# SSTuino_Evo.net
KiCad netlist of a schematic drawn in EAGLE
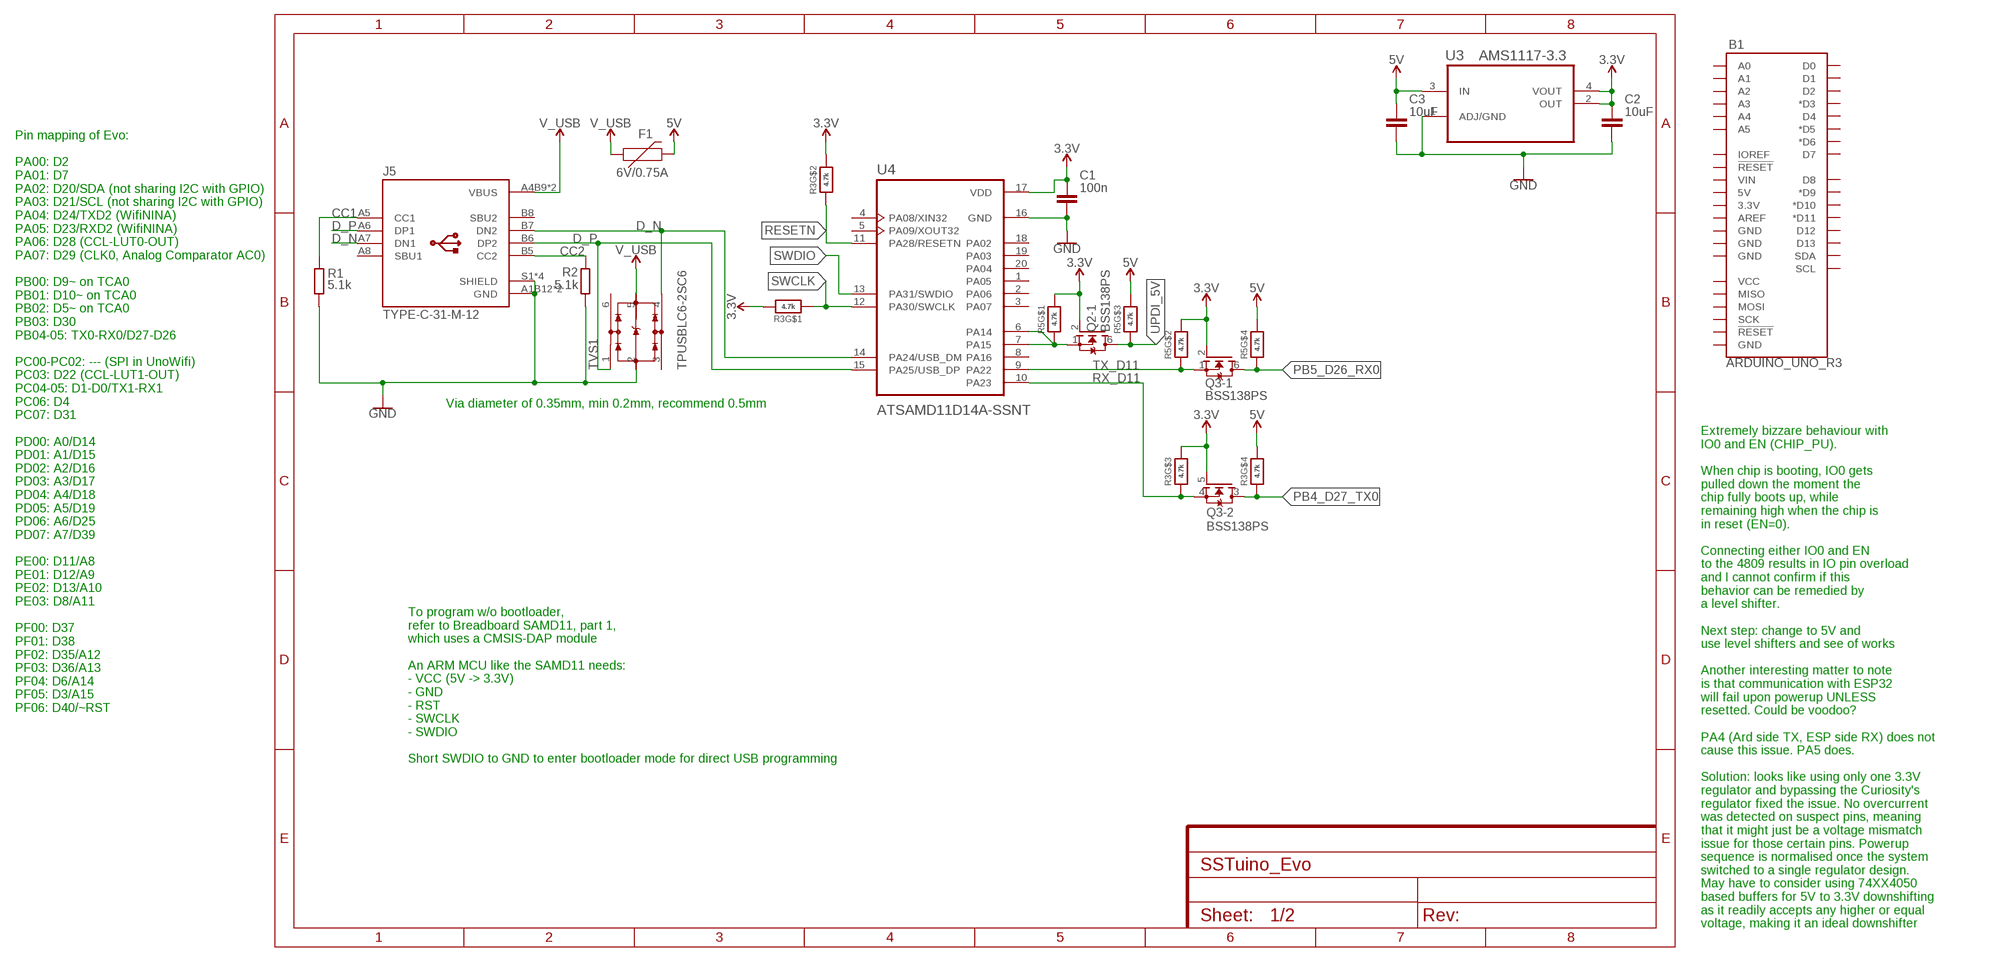
[diagram p0: schematic, sheet 1]
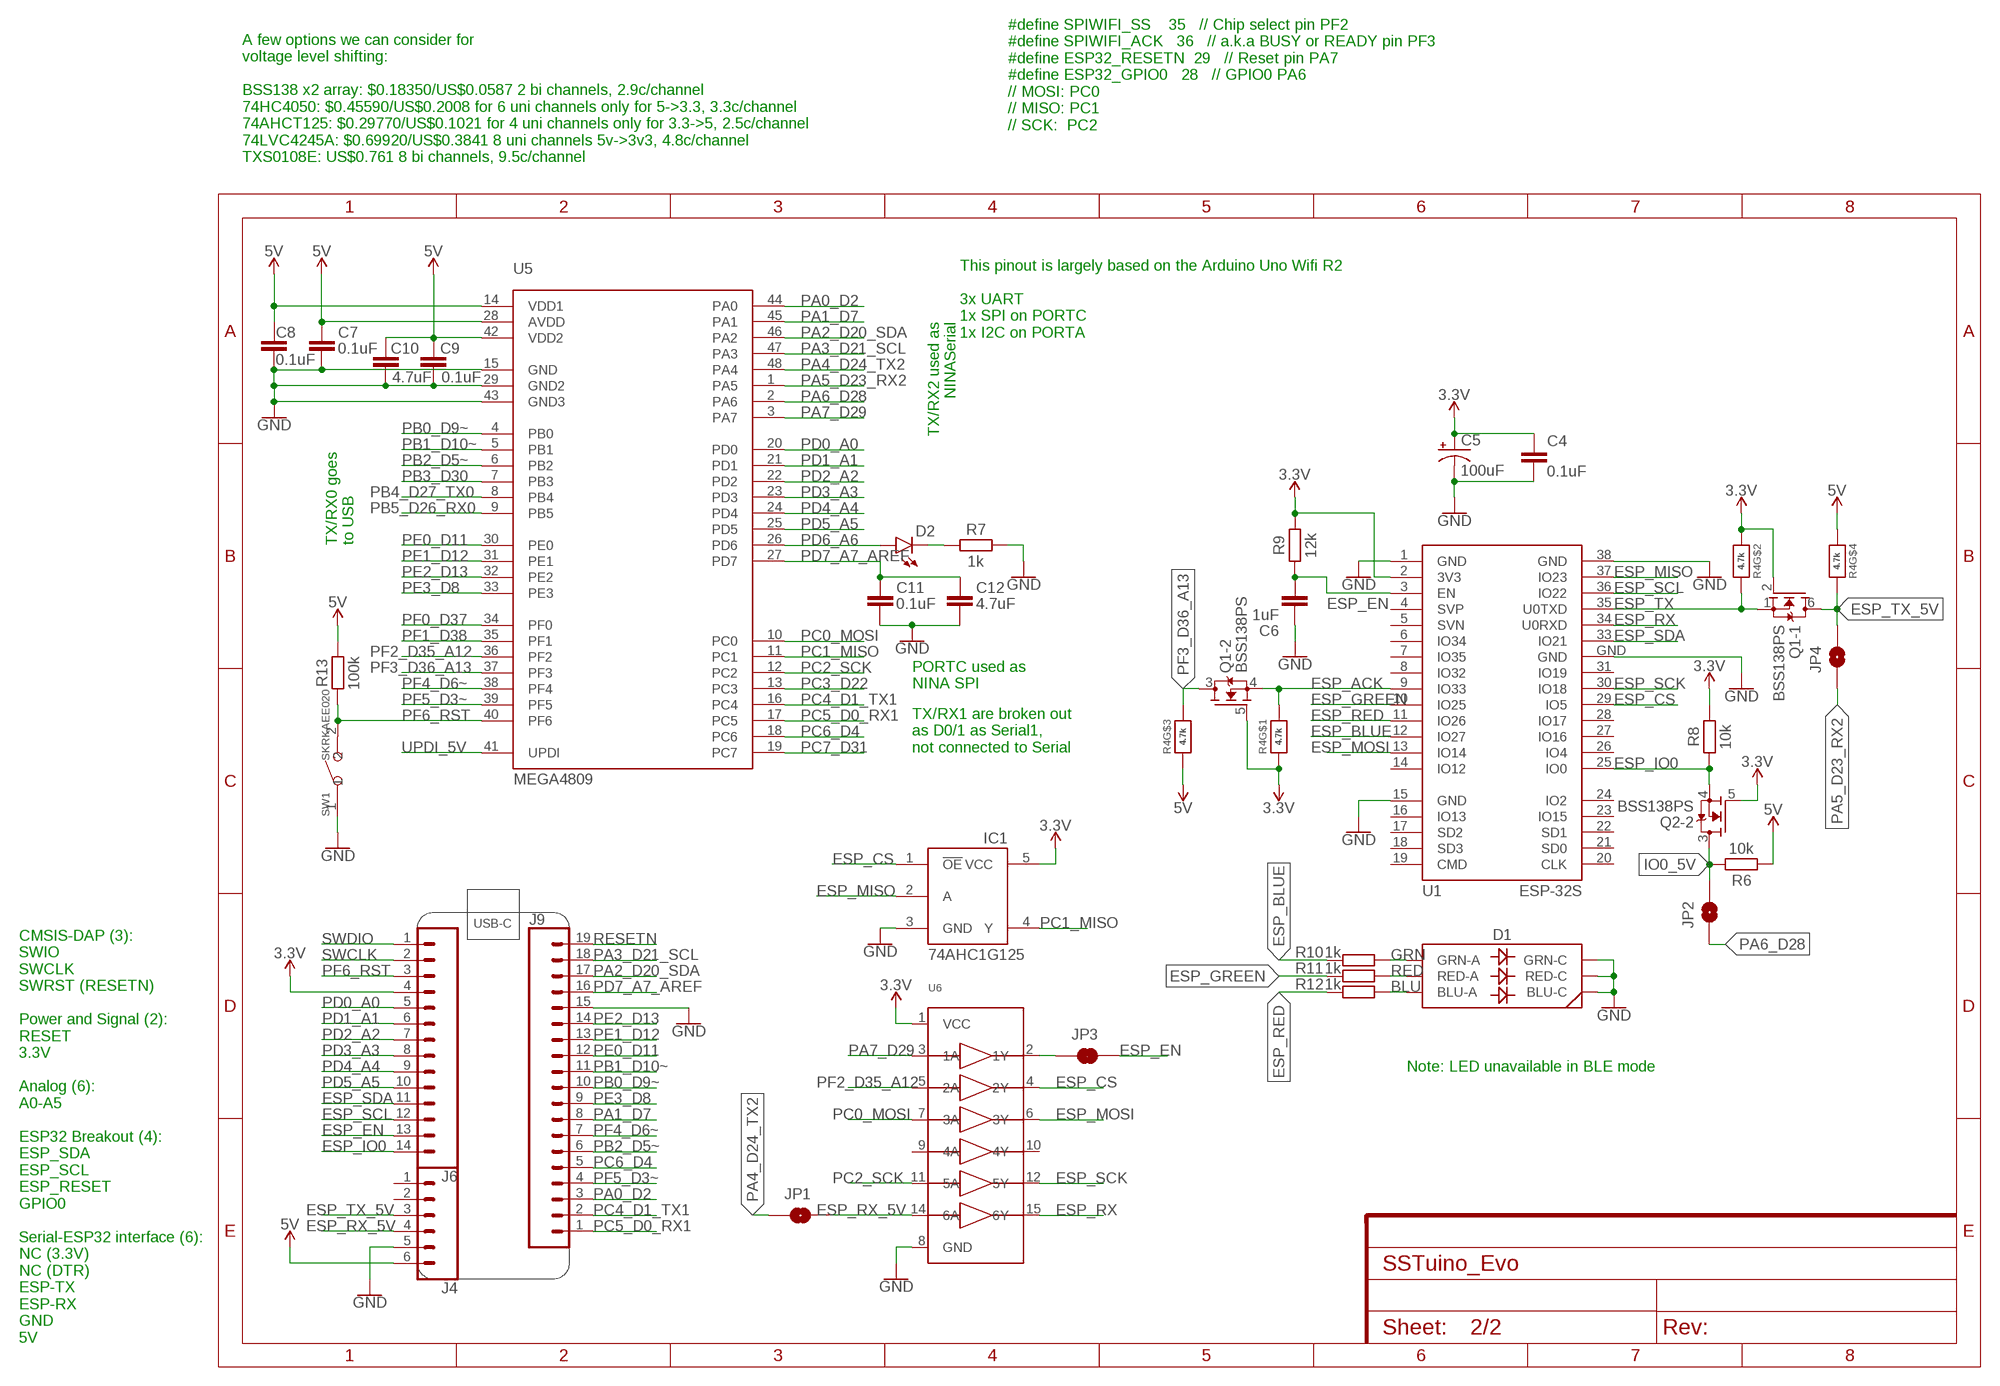
[diagram p1: schematic, sheet 2]

(export (version "E")
  (design (tool "Eeschema 10.0.6"))
  (components
    (comp (ref "B1")
      (value "ARDUINO_UNO_R3")
      (footprint "eagle-import:ARDUINO_R3")
      (libsource (lib "eagle-import") (part "ARDUINO_UNO_R3"))
    )
    (comp (ref "C1")
      (value "100n")
      (footprint "eagle-import:CAPC1005X60")
      (libsource (lib "eagle-import") (part "CCHIP-0402(1005-METRIC)_"))
    )
    (comp (ref "C2")
      (value "10uF")
      (footprint "eagle-import:CAPC1608X85")
      (libsource (lib "eagle-import") (part "CCHIP-0603(1608-METRIC)_"))
    )
    (comp (ref "C3")
      (value "10uF")
      (footprint "eagle-import:CAPC1608X85")
      (libsource (lib "eagle-import") (part "CCHIP-0603(1608-METRIC)_"))
    )
    (comp (ref "F1")
      (value "6V/0.75A")
      (footprint "eagle-import:1206")
      (fields (field (name "LCSC_PART") "C99563"))
      (libsource (lib "eagle-import") (part "PPTC_THREE-QUARTER-AMP"))
    )
    (comp (ref "J5")
      (value "TYPE-C-31-M-12")
      (footprint "eagle-import:HRO_TYPE-C-31-M-12")
      (fields (field (name "MF") "HRO Electronics Co., Ltd.") (field (name "LCSC_PART") "C165948"))
      (libsource (lib "eagle-import") (part "TYPE-C-31-M-12"))
    )
    (comp (ref "Q2")
      (value "BSS138PS")
      (footprint "eagle-import:ARDUINO-TRANSISTORS_SOT363")
      (fields (field (name "MANUFACTURER") "NXP") (field (name "LCSC_PART") "C193381"))
      (libsource (lib "eagle-import") (part "BSS138PS"))
    )
    (comp (ref "Q3")
      (value "BSS138PS")
      (footprint "eagle-import:ARDUINO-TRANSISTORS_SOT363")
      (fields (field (name "MANUFACTURER") "NXP") (field (name "LCSC_PART") "C193381"))
      (libsource (lib "eagle-import") (part "BSS138PS"))
    )
    (comp (ref "R1")
      (value "5.1k")
      (footprint "eagle-import:RESC1005X40")
      (libsource (lib "eagle-import") (part "RCHIP-0402(1005-METRIC)_"))
    )
    (comp (ref "R2")
      (value "5.1k")
      (footprint "eagle-import:RESC1005X40")
      (libsource (lib "eagle-import") (part "RCHIP-0402(1005-METRIC)_"))
    )
    (comp (ref "R3")
      (value "4.7k")
      (footprint "eagle-import:RESPACK_4X0402")
      (fields (field (name "LCSC_PART") "C1980"))
      (libsource (lib "eagle-import") (part "RESISTOR_4PACK0402"))
    )
    (comp (ref "R5")
      (value "4.7k")
      (footprint "eagle-import:RESPACK_4X0402")
      (fields (field (name "LCSC_PART") "C1980"))
      (libsource (lib "eagle-import") (part "RESISTOR_4PACK0402"))
    )
    (comp (ref "TVS1")
      (value "TPUSBLC6-2SC6")
      (footprint "eagle-import:SOT95P280X110-6N")
      (fields (field (name "LCSC_PART") "C558442"))
      (libsource (lib "eagle-import") (part "TPUSBLC6-2SC6"))
    )
    (comp (ref "U3")
      (value "AMS1117-3.3")
      (footprint "eagle-import:SOT230P696X180-4N")
      (fields (field (name "MPN") "LM1117MP-3.3") (field (name "LCSC_PART") "C6186"))
      (libsource (lib "eagle-import") (part "LM1117MP-3.3"))
    )
    (comp (ref "U4")
      (value "ATSAMD11D14A-SSNT")
      (footprint "eagle-import:SOIC127P1030X265-20N")
      (fields (field (name "MF") "Microchip") (field (name "LCSC_PART") "C2053599"))
      (libsource (lib "eagle-import") (part "ATSAMD11D14A-SSNT"))
    )
    (comp (ref "C4")
      (value "0.1uF")
      (footprint "eagle-import:CAPC1005X60")
      (libsource (lib "eagle-import") (part "CCHIP-0402(1005-METRIC)_"))
    )
    (comp (ref "C5")
      (value "100uF")
      (footprint "eagle-import:CAPMP3216X180N")
      (libsource (lib "eagle-import") (part "C-POL-USTANTALUM-1206(3216-METRIC)_"))
    )
    (comp (ref "C6")
      (value "1uF")
      (footprint "eagle-import:CAPC1005X60")
      (libsource (lib "eagle-import") (part "CCHIP-0402(1005-METRIC)_"))
    )
    (comp (ref "C7")
      (value "0.1uF")
      (footprint "eagle-import:CAPC1005X60")
      (libsource (lib "eagle-import") (part "CCHIP-0402(1005-METRIC)_"))
    )
    (comp (ref "C8")
      (value "0.1uF")
      (footprint "eagle-import:CAPC1005X60")
      (libsource (lib "eagle-import") (part "CCHIP-0402(1005-METRIC)_"))
    )
    (comp (ref "C9")
      (value "0.1uF")
      (footprint "eagle-import:CAPC1005X60")
      (libsource (lib "eagle-import") (part "CCHIP-0402(1005-METRIC)_"))
    )
    (comp (ref "C10")
      (value "4.7uF")
      (footprint "eagle-import:CAPC1005X60")
      (libsource (lib "eagle-import") (part "CCHIP-0402(1005-METRIC)_"))
    )
    (comp (ref "C11")
      (value "0.1uF")
      (footprint "eagle-import:CAPC1005X60")
      (libsource (lib "eagle-import") (part "CCHIP-0402(1005-METRIC)_"))
    )
    (comp (ref "C12")
      (value "4.7uF")
      (footprint "eagle-import:CAPC1005X60")
      (libsource (lib "eagle-import") (part "CCHIP-0402(1005-METRIC)_"))
    )
    (comp (ref "D1")
      (value "LED-RGBTC5050RGBF08")
      (footprint "eagle-import:LED-TRICOLOR-5050")
      (libsource (lib "eagle-import") (part "LED-RGBTC5050RGBF08"))
    )
    (comp (ref "D2")
      (value "LED0603")
      (footprint "eagle-import:LED-0603")
      (libsource (lib "eagle-import") (part "LED0603"))
    )
    (comp (ref "IC1")
      (value "74AHC1G125")
      (footprint "eagle-import:SOT23-5L")
      (fields (field (name "LCSC_PART") "C124295"))
      (libsource (lib "eagle-import") (part "74AHC1G125"))
    )
    (comp (ref "J4")
      (value "CONN_06NO_SILK_FEMALE_PTH")
      (footprint "eagle-import:1X06_NO_SILK")
      (libsource (lib "eagle-import") (part "CONN_06NO_SILK_FEMALE_PTH"))
    )
    (comp (ref "J6")
      (value "CONN_14NO_SILK")
      (footprint "eagle-import:1X14_NO_SILK")
      (libsource (lib "eagle-import") (part "CONN_14NO_SILK"))
    )
    (comp (ref "J9")
      (value "CONN_191X19_NO_SILK")
      (footprint "eagle-import:1X19_NO_SILK")
      (libsource (lib "eagle-import") (part "CONN_191X19_NO_SILK"))
    )
    (comp (ref "JP1")
      (value "JUMPER-SMT_2_NO_SILK")
      (footprint "eagle-import:SMT-JUMPER_2_NO_SILK")
      (libsource (lib "eagle-import") (part "JUMPER-SMT_2_NO_SILK"))
    )
    (comp (ref "JP2")
      (value "JUMPER-SMT_2_NO_SILK")
      (footprint "eagle-import:SMT-JUMPER_2_NO_SILK")
      (libsource (lib "eagle-import") (part "JUMPER-SMT_2_NO_SILK"))
    )
    (comp (ref "JP3")
      (value "JUMPER-SMT_2_NC_TRACE_SILK")
      (footprint "eagle-import:SMT-JUMPER_2_NC_TRACE_SILK")
      (libsource (lib "eagle-import") (part "JUMPER-SMT_2_NC_TRACE_SILK"))
    )
    (comp (ref "JP4")
      (value "JUMPER-SMT_2_NO_SILK")
      (footprint "eagle-import:SMT-JUMPER_2_NO_SILK")
      (libsource (lib "eagle-import") (part "JUMPER-SMT_2_NO_SILK"))
    )
    (comp (ref "Q1")
      (value "BSS138PS")
      (footprint "eagle-import:ARDUINO-TRANSISTORS_SOT363")
      (fields (field (name "MANUFACTURER") "NXP") (field (name "LCSC_PART") "C193381"))
      (libsource (lib "eagle-import") (part "BSS138PS"))
    )
    (comp (ref "R4")
      (value "4.7k")
      (footprint "eagle-import:RESPACK_4X0402")
      (fields (field (name "LCSC_PART") "C1980"))
      (libsource (lib "eagle-import") (part "RESISTOR_4PACK0402"))
    )
    (comp (ref "R6")
      (value "10k")
      (footprint "eagle-import:RESC1005X40")
      (libsource (lib "eagle-import") (part "RCHIP-0402(1005-METRIC)_"))
    )
    (comp (ref "R7")
      (value "1k")
      (footprint "eagle-import:RESC1005X40")
      (libsource (lib "eagle-import") (part "RCHIP-0402(1005-METRIC)_"))
    )
    (comp (ref "R8")
      (value "10k")
      (footprint "eagle-import:RESC1005X40")
      (libsource (lib "eagle-import") (part "RCHIP-0402(1005-METRIC)_"))
    )
    (comp (ref "R9")
      (value "12k")
      (footprint "eagle-import:RESC1005X40")
      (libsource (lib "eagle-import") (part "RCHIP-0402(1005-METRIC)_"))
    )
    (comp (ref "R10")
      (value "1k")
      (footprint "eagle-import:RESC1005X40")
      (libsource (lib "eagle-import") (part "RCHIP-0402(1005-METRIC)_"))
    )
    (comp (ref "R11")
      (value "1k")
      (footprint "eagle-import:RESC1005X40")
      (libsource (lib "eagle-import") (part "RCHIP-0402(1005-METRIC)_"))
    )
    (comp (ref "R12")
      (value "1k")
      (footprint "eagle-import:RESC1005X40")
      (libsource (lib "eagle-import") (part "RCHIP-0402(1005-METRIC)_"))
    )
    (comp (ref "R13")
      (value "100k")
      (footprint "eagle-import:RESC1005X40")
      (libsource (lib "eagle-import") (part "RCHIP-0402(1005-METRIC)_"))
    )
    (comp (ref "SW1")
      (value "SKRKAEE020")
      (footprint "eagle-import:SW2-2.6-3.9X2.9X1.5+0.4MM")
      (fields (field (name "LCSC_PART") "C115357") (field (name "LCSC_PART_1") "C115357"))
      (libsource (lib "eagle-import") (part "SMD-BUTTON(2P-3.9X2.9X1.5+0.4MM)-SKRKAEE020"))
    )
    (comp (ref "U1")
      (value "ESP-32S")
      (footprint "eagle-import:ESP-32S")
      (libsource (lib "eagle-import") (part "ESP-32S"))
    )
    (comp (ref "U5")
      (value "MEGA4809")
      (footprint "eagle-import:TQFP48")
      (fields (field (name "LCSC_PART") "C189475"))
      (libsource (lib "eagle-import") (part "MEGA4809"))
    )
    (comp (ref "U6")
      (value "74HC4050DTSSOP")
      (footprint "eagle-import:TSSOP16")
      (fields (field (name "LCSC_PART") "C43181"))
      (libsource (lib "eagle-import") (part "74HC4050DTSSOP"))
    )
  )
  (nets
    (net (code "1") (name "3.3V") (class "Default")
      (node (ref "C1") (pin "1") (pinfunction "1_1") (pintype "passive"))
      (node (ref "C2") (pin "1") (pinfunction "1_1") (pintype "passive"))
      (node (ref "C4") (pin "1") (pinfunction "1_1") (pintype "passive"))
      (node (ref "C5") (pin "1") (pinfunction "+_1") (pintype "passive"))
      (node (ref "IC1") (pin "5") (pinfunction "VCC_5") (pintype "power_in"))
      (node (ref "J6") (pin "4") (pinfunction "4_4") (pintype "passive"))
      (node (ref "Q1") (pin "2") (pinfunction "G_2") (pintype "passive"))
      (node (ref "Q1") (pin "5") (pinfunction "G_5") (pintype "passive"))
      (node (ref "Q2") (pin "2") (pinfunction "G_2") (pintype "passive"))
      (node (ref "Q2") (pin "5") (pinfunction "G_5") (pintype "passive"))
      (node (ref "Q3") (pin "2") (pinfunction "G_2") (pintype "passive"))
      (node (ref "Q3") (pin "5") (pinfunction "G_5") (pintype "passive"))
      (node (ref "R3") (pin "6") (pinfunction "2_6") (pintype "passive"))
      (node (ref "R3") (pin "7") (pinfunction "2_7") (pintype "passive"))
      (node (ref "R3") (pin "8") (pinfunction "2_8") (pintype "passive"))
      (node (ref "R4") (pin "1") (pinfunction "1_1") (pintype "passive"))
      (node (ref "R4") (pin "2") (pinfunction "1_2") (pintype "passive"))
      (node (ref "R5") (pin "7") (pinfunction "2_7") (pintype "passive"))
      (node (ref "R5") (pin "8") (pinfunction "2_8") (pintype "passive"))
      (node (ref "R8") (pin "2") (pinfunction "2_2") (pintype "passive"))
      (node (ref "R9") (pin "2") (pinfunction "2_2") (pintype "passive"))
      (node (ref "U1") (pin "2") (pinfunction "3V3_2") (pintype "power_in"))
      (node (ref "U3") (pin "2") (pinfunction "OUT_2") (pintype "output"))
      (node (ref "U3") (pin "4") (pinfunction "VOUT_4") (pintype "output"))
      (node (ref "U4") (pin "17") (pinfunction "VDD_17") (pintype "power_in"))
      (node (ref "U6") (pin "1") (pinfunction "VCC_1") (pintype "bidirectional"))
    )
    (net (code "2") (name "5V") (class "Default")
      (node (ref "C10") (pin "1") (pinfunction "1_1") (pintype "passive"))
      (node (ref "C3") (pin "1") (pinfunction "1_1") (pintype "passive"))
      (node (ref "C7") (pin "1") (pinfunction "1_1") (pintype "passive"))
      (node (ref "C8") (pin "1") (pinfunction "1_1") (pintype "passive"))
      (node (ref "C9") (pin "1") (pinfunction "1_1") (pintype "passive"))
      (node (ref "F1") (pin "2") (pinfunction "2_2") (pintype "bidirectional"))
      (node (ref "J4") (pin "6") (pinfunction "6_6") (pintype "passive"))
      (node (ref "R13") (pin "2") (pinfunction "2_2") (pintype "passive"))
      (node (ref "R3") (pin "5") (pinfunction "2_5") (pintype "passive"))
      (node (ref "R4") (pin "3") (pinfunction "1_3") (pintype "passive"))
      (node (ref "R4") (pin "4") (pinfunction "1_4") (pintype "passive"))
      (node (ref "R5") (pin "5") (pinfunction "2_5") (pintype "passive"))
      (node (ref "R5") (pin "6") (pinfunction "2_6") (pintype "passive"))
      (node (ref "R6") (pin "1") (pinfunction "1_1") (pintype "passive"))
      (node (ref "U3") (pin "3") (pinfunction "IN_3") (pintype "input"))
      (node (ref "U5") (pin "14") (pinfunction "VDD1_14") (pintype "bidirectional"))
      (node (ref "U5") (pin "28") (pinfunction "AVDD_28") (pintype "bidirectional"))
      (node (ref "U5") (pin "42") (pinfunction "VDD2_42") (pintype "bidirectional"))
    )
    (net (code "3") (name "BLU") (class "Default")
      (node (ref "D1") (pin "6") (pinfunction "BLU-A_6") (pintype "bidirectional"))
      (node (ref "R12") (pin "2") (pinfunction "2_2") (pintype "passive"))
    )
    (net (code "4") (name "CC1") (class "Default")
      (node (ref "J5") (pin "A5") (pinfunction "CC1_A5") (pintype "bidirectional"))
      (node (ref "R1") (pin "1") (pinfunction "1_1") (pintype "passive"))
    )
    (net (code "5") (name "CC2") (class "Default")
      (node (ref "J5") (pin "B5") (pinfunction "CC2_B5") (pintype "bidirectional"))
      (node (ref "R2") (pin "2") (pinfunction "2_2") (pintype "passive"))
    )
    (net (code "6") (name "D_N") (class "Default")
      (node (ref "J5") (pin "A7") (pinfunction "DN1_A7") (pintype "bidirectional"))
      (node (ref "J5") (pin "B7") (pinfunction "DN2_B7") (pintype "bidirectional"))
      (node (ref "TVS1") (pin "4") (pinfunction "IO3_4") (pintype "passive"))
      (node (ref "U4") (pin "14") (pinfunction "PA24/USB_DM_14") (pintype "bidirectional"))
    )
    (net (code "7") (name "D_P") (class "Default")
      (node (ref "J5") (pin "A6") (pinfunction "DP1_A6") (pintype "bidirectional"))
      (node (ref "J5") (pin "B6") (pinfunction "DP2_B6") (pintype "bidirectional"))
      (node (ref "TVS1") (pin "1") (pinfunction "IO1_1") (pintype "passive"))
      (node (ref "U4") (pin "15") (pinfunction "PA25/USB_DP_15") (pintype "bidirectional"))
    )
    (net (code "8") (name "ESP_ACK") (class "Default")
      (node (ref "Q1") (pin "4") (pinfunction "S_4") (pintype "passive"))
      (node (ref "R4") (pin "8") (pinfunction "2_8") (pintype "passive"))
      (node (ref "U1") (pin "9") (pinfunction "IO33_9") (pintype "bidirectional"))
    )
    (net (code "9") (name "ESP_BLUE") (class "Default")
      (node (ref "R10") (pin "1") (pinfunction "1_1") (pintype "passive"))
      (node (ref "U1") (pin "12") (pinfunction "IO27_12") (pintype "bidirectional"))
    )
    (net (code "10") (name "ESP_CS") (class "Default")
      (node (ref "IC1") (pin "1") (pinfunction "~{OE}_1") (pintype "input"))
      (node (ref "U1") (pin "29") (pinfunction "IO5_29") (pintype "bidirectional"))
      (node (ref "U6") (pin "4") (pinfunction "2Y_4") (pintype "bidirectional"))
    )
    (net (code "11") (name "ESP_EN") (class "Default")
      (node (ref "C6") (pin "2") (pinfunction "2_2") (pintype "passive"))
      (node (ref "J6") (pin "13") (pinfunction "13_13") (pintype "passive"))
      (node (ref "JP3") (pin "2") (pinfunction "2_2") (pintype "passive"))
      (node (ref "R9") (pin "1") (pinfunction "1_1") (pintype "passive"))
      (node (ref "U1") (pin "3") (pinfunction "EN_3") (pintype "input"))
    )
    (net (code "12") (name "ESP_GREEN") (class "Default")
      (node (ref "R11") (pin "1") (pinfunction "1_1") (pintype "passive"))
      (node (ref "U1") (pin "10") (pinfunction "IO25_10") (pintype "bidirectional"))
    )
    (net (code "13") (name "ESP_IO0") (class "Default")
      (node (ref "J6") (pin "14") (pinfunction "14_14") (pintype "passive"))
      (node (ref "Q2") (pin "4") (pinfunction "S_4") (pintype "passive"))
      (node (ref "R8") (pin "1") (pinfunction "1_1") (pintype "passive"))
      (node (ref "U1") (pin "25") (pinfunction "IO0_25") (pintype "bidirectional"))
    )
    (net (code "14") (name "ESP_MISO") (class "Default")
      (node (ref "IC1") (pin "2") (pinfunction "A_2") (pintype "input"))
      (node (ref "U1") (pin "37") (pinfunction "IO23_37") (pintype "bidirectional"))
    )
    (net (code "15") (name "ESP_MOSI") (class "Default")
      (node (ref "U1") (pin "13") (pinfunction "IO14_13") (pintype "bidirectional"))
      (node (ref "U6") (pin "6") (pinfunction "3Y_6") (pintype "bidirectional"))
    )
    (net (code "16") (name "ESP_RED") (class "Default")
      (node (ref "R12") (pin "1") (pinfunction "1_1") (pintype "passive"))
      (node (ref "U1") (pin "11") (pinfunction "IO26_11") (pintype "bidirectional"))
    )
    (net (code "17") (name "ESP_RX") (class "Default")
      (node (ref "U1") (pin "34") (pinfunction "U0RXD_34") (pintype "bidirectional"))
      (node (ref "U6") (pin "15") (pinfunction "6Y_15") (pintype "bidirectional"))
    )
    (net (code "18") (name "ESP_RX_5V") (class "Default")
      (node (ref "J4") (pin "4") (pinfunction "4_4") (pintype "passive"))
      (node (ref "JP1") (pin "2") (pinfunction "2_2") (pintype "passive"))
      (node (ref "U6") (pin "14") (pinfunction "6A_14") (pintype "bidirectional"))
    )
    (net (code "19") (name "ESP_SCK") (class "Default")
      (node (ref "U1") (pin "30") (pinfunction "IO18_30") (pintype "bidirectional"))
      (node (ref "U6") (pin "12") (pinfunction "5Y_12") (pintype "bidirectional"))
    )
    (net (code "20") (name "ESP_SCL") (class "Default")
      (node (ref "J6") (pin "12") (pinfunction "12_12") (pintype "passive"))
      (node (ref "U1") (pin "36") (pinfunction "IO22_36") (pintype "bidirectional"))
    )
    (net (code "21") (name "ESP_SDA") (class "Default")
      (node (ref "J6") (pin "11") (pinfunction "11_11") (pintype "passive"))
      (node (ref "U1") (pin "33") (pinfunction "IO21_33") (pintype "bidirectional"))
    )
    (net (code "22") (name "ESP_TX") (class "Default")
      (node (ref "Q1") (pin "1") (pinfunction "S_1") (pintype "passive"))
      (node (ref "R4") (pin "7") (pinfunction "2_7") (pintype "passive"))
      (node (ref "U1") (pin "35") (pinfunction "U0TXD_35") (pintype "bidirectional"))
    )
    (net (code "23") (name "ESP_TX_5V") (class "Default")
      (node (ref "J4") (pin "3") (pinfunction "3_3") (pintype "passive"))
      (node (ref "JP4") (pin "2") (pinfunction "2_2") (pintype "passive"))
      (node (ref "Q1") (pin "6") (pinfunction "D_6") (pintype "passive"))
      (node (ref "R4") (pin "5") (pinfunction "2_5") (pintype "passive"))
    )
    (net (code "24") (name "GND") (class "Default")
      (node (ref "C1") (pin "2") (pinfunction "2_2") (pintype "passive"))
      (node (ref "C10") (pin "2") (pinfunction "2_2") (pintype "passive"))
      (node (ref "C11") (pin "2") (pinfunction "2_2") (pintype "passive"))
      (node (ref "C12") (pin "2") (pinfunction "2_2") (pintype "passive"))
      (node (ref "C2") (pin "2") (pinfunction "2_2") (pintype "passive"))
      (node (ref "C3") (pin "2") (pinfunction "2_2") (pintype "passive"))
      (node (ref "C4") (pin "2") (pinfunction "2_2") (pintype "passive"))
      (node (ref "C5") (pin "2") (pinfunction "-_2") (pintype "passive"))
      (node (ref "C6") (pin "1") (pinfunction "1_1") (pintype "passive"))
      (node (ref "C7") (pin "2") (pinfunction "2_2") (pintype "passive"))
      (node (ref "C8") (pin "2") (pinfunction "2_2") (pintype "passive"))
      (node (ref "C9") (pin "2") (pinfunction "2_2") (pintype "passive"))
      (node (ref "D1") (pin "1") (pinfunction "BLU-C_1") (pintype "bidirectional"))
      (node (ref "D1") (pin "2") (pinfunction "RED-C_2") (pintype "bidirectional"))
      (node (ref "D1") (pin "3") (pinfunction "GRN-C_3") (pintype "bidirectional"))
      (node (ref "IC1") (pin "3") (pinfunction "GND_3") (pintype "power_in"))
      (node (ref "J4") (pin "5") (pinfunction "5_5") (pintype "passive"))
      (node (ref "J5") (pin "A1B12") (pinfunction "GND_A1B12") (pintype "power_in"))
      (node (ref "J5") (pin "B1A12") (pinfunction "GND_B1A12") (pintype "power_in"))
      (node (ref "J5") (pin "S1") (pinfunction "SHIELD_S1") (pintype "passive"))
      (node (ref "J5") (pin "S2") (pinfunction "SHIELD_S2") (pintype "passive"))
      (node (ref "J5") (pin "S3") (pinfunction "SHIELD_S3") (pintype "passive"))
      (node (ref "J5") (pin "S4") (pinfunction "SHIELD_S4") (pintype "passive"))
      (node (ref "J9") (pin "15") (pinfunction "15_15") (pintype "passive"))
      (node (ref "R1") (pin "2") (pinfunction "2_2") (pintype "passive"))
      (node (ref "R2") (pin "1") (pinfunction "1_1") (pintype "passive"))
      (node (ref "R7") (pin "2") (pinfunction "2_2") (pintype "passive"))
      (node (ref "SW1") (pin "1") (pinfunction "1_1") (pintype "bidirectional"))
      (node (ref "TVS1") (pin "2") (pinfunction "VSS_2") (pintype "power_in"))
      (node (ref "U1") (pin "1") (pinfunction "GND_1") (pintype "power_in"))
      (node (ref "U1") (pin "15") (pinfunction "GND_15") (pintype "power_in"))
      (node (ref "U1") (pin "38") (pinfunction "GND_38") (pintype "power_in"))
      (node (ref "U1") (pin "GND") (pinfunction "GND_GND") (pintype "power_in"))
      (node (ref "U3") (pin "1") (pinfunction "ADJ/GND_1") (pintype "passive"))
      (node (ref "U4") (pin "16") (pinfunction "GND_16") (pintype "power_in"))
      (node (ref "U5") (pin "15") (pinfunction "GND_15") (pintype "bidirectional"))
      (node (ref "U5") (pin "29") (pinfunction "GND2_29") (pintype "bidirectional"))
      (node (ref "U5") (pin "43") (pinfunction "GND3_43") (pintype "bidirectional"))
      (node (ref "U6") (pin "8") (pinfunction "GND_8") (pintype "bidirectional"))
    )
    (net (code "25") (name "GRN") (class "Default")
      (node (ref "D1") (pin "4") (pinfunction "GRN-A_4") (pintype "bidirectional"))
      (node (ref "R10") (pin "2") (pinfunction "2_2") (pintype "passive"))
    )
    (net (code "26") (name "IO0_5V") (class "Default")
      (node (ref "JP2") (pin "2") (pinfunction "2_2") (pintype "passive"))
      (node (ref "Q2") (pin "3") (pinfunction "D_3") (pintype "passive"))
      (node (ref "R6") (pin "2") (pinfunction "2_2") (pintype "passive"))
    )
    (net (code "27") (name "Net-(D2-PadC)") (class "Default")
      (node (ref "D2") (pin "C") (pinfunction "C_C") (pintype "passive"))
      (node (ref "R7") (pin "1") (pinfunction "1_1") (pintype "passive"))
    )
    (net (code "28") (name "Net-(Q2A-S)") (class "Default")
      (node (ref "Q2") (pin "1") (pinfunction "S_1") (pintype "passive"))
      (node (ref "R5") (pin "1") (pinfunction "1_1") (pintype "passive"))
      (node (ref "U4") (pin "6") (pinfunction "PA14_6") (pintype "bidirectional"))
      (node (ref "U4") (pin "7") (pinfunction "PA15_7") (pintype "bidirectional"))
    )
    (net (code "29") (name "Net-(U6-1Y)") (class "Default")
      (node (ref "JP3") (pin "1") (pinfunction "1_1") (pintype "passive"))
      (node (ref "U6") (pin "2") (pinfunction "1Y_2") (pintype "bidirectional"))
    )
    (net (code "30") (name "PA0_D2") (class "Default")
      (node (ref "J9") (pin "3") (pinfunction "3_3") (pintype "passive"))
      (node (ref "U5") (pin "44") (pinfunction "PA0_44") (pintype "bidirectional"))
    )
    (net (code "31") (name "PA1_D7") (class "Default")
      (node (ref "J9") (pin "8") (pinfunction "8_8") (pintype "passive"))
      (node (ref "U5") (pin "45") (pinfunction "PA1_45") (pintype "bidirectional"))
    )
    (net (code "32") (name "PA2_D20_SDA") (class "Default")
      (node (ref "J9") (pin "17") (pinfunction "17_17") (pintype "passive"))
      (node (ref "U5") (pin "46") (pinfunction "PA2_46") (pintype "bidirectional"))
    )
    (net (code "33") (name "PA3_D21_SCL") (class "Default")
      (node (ref "J9") (pin "18") (pinfunction "18_18") (pintype "passive"))
      (node (ref "U5") (pin "47") (pinfunction "PA3_47") (pintype "bidirectional"))
    )
    (net (code "34") (name "PA4_D24_TX2") (class "Default")
      (node (ref "JP1") (pin "1") (pinfunction "1_1") (pintype "passive"))
      (node (ref "U5") (pin "48") (pinfunction "PA4_48") (pintype "bidirectional"))
    )
    (net (code "35") (name "PA5_D23_RX2") (class "Default")
      (node (ref "JP4") (pin "1") (pinfunction "1_1") (pintype "passive"))
      (node (ref "U5") (pin "1") (pinfunction "PA5_1") (pintype "bidirectional"))
    )
    (net (code "36") (name "PA6_D28") (class "Default")
      (node (ref "JP2") (pin "1") (pinfunction "1_1") (pintype "passive"))
      (node (ref "U5") (pin "2") (pinfunction "PA6_2") (pintype "bidirectional"))
    )
    (net (code "37") (name "PA7_D29") (class "Default")
      (node (ref "U5") (pin "3") (pinfunction "PA7_3") (pintype "bidirectional"))
      (node (ref "U6") (pin "3") (pinfunction "1A_3") (pintype "bidirectional"))
    )
    (net (code "38") (name "PB0_D9~{}") (class "Default")
      (node (ref "J9") (pin "10") (pinfunction "10_10") (pintype "passive"))
      (node (ref "U5") (pin "4") (pinfunction "PB0_4") (pintype "bidirectional"))
    )
    (net (code "39") (name "PB1_D10~{}") (class "Default")
      (node (ref "J9") (pin "11") (pinfunction "11_11") (pintype "passive"))
      (node (ref "U5") (pin "5") (pinfunction "PB1_5") (pintype "bidirectional"))
    )
    (net (code "40") (name "PB2_D5~{}") (class "Default")
      (node (ref "J9") (pin "6") (pinfunction "6_6") (pintype "passive"))
      (node (ref "U5") (pin "6") (pinfunction "PB2_6") (pintype "bidirectional"))
    )
    (net (code "41") (name "PB3_D30") (class "Default")
      (node (ref "U5") (pin "7") (pinfunction "PB3_7") (pintype "bidirectional"))
    )
    (net (code "42") (name "PB4_D27_TX0") (class "Default")
      (node (ref "Q3") (pin "3") (pinfunction "D_3") (pintype "passive"))
      (node (ref "R3") (pin "4") (pinfunction "1_4") (pintype "passive"))
      (node (ref "U5") (pin "8") (pinfunction "PB4_8") (pintype "bidirectional"))
    )
    (net (code "43") (name "PB5_D26_RX0") (class "Default")
      (node (ref "Q3") (pin "6") (pinfunction "D_6") (pintype "passive"))
      (node (ref "R5") (pin "4") (pinfunction "1_4") (pintype "passive"))
      (node (ref "U5") (pin "9") (pinfunction "PB5_9") (pintype "bidirectional"))
    )
    (net (code "44") (name "PC0_MOSI") (class "Default")
      (node (ref "U5") (pin "10") (pinfunction "PC0_10") (pintype "bidirectional"))
      (node (ref "U6") (pin "7") (pinfunction "3A_7") (pintype "bidirectional"))
    )
    (net (code "45") (name "PC1_MISO") (class "Default")
      (node (ref "IC1") (pin "4") (pinfunction "Y_4") (pintype "output"))
      (node (ref "U5") (pin "11") (pinfunction "PC1_11") (pintype "bidirectional"))
    )
    (net (code "46") (name "PC2_SCK") (class "Default")
      (node (ref "U5") (pin "12") (pinfunction "PC2_12") (pintype "bidirectional"))
      (node (ref "U6") (pin "11") (pinfunction "5A_11") (pintype "bidirectional"))
    )
    (net (code "47") (name "PC3_D22") (class "Default")
      (node (ref "U5") (pin "13") (pinfunction "PC3_13") (pintype "bidirectional"))
    )
    (net (code "48") (name "PC4_D1_TX1") (class "Default")
      (node (ref "J9") (pin "2") (pinfunction "2_2") (pintype "passive"))
      (node (ref "U5") (pin "16") (pinfunction "PC4_16") (pintype "bidirectional"))
    )
    (net (code "49") (name "PC5_D0_RX1") (class "Default")
      (node (ref "J9") (pin "1") (pinfunction "1_1") (pintype "passive"))
      (node (ref "U5") (pin "17") (pinfunction "PC5_17") (pintype "bidirectional"))
    )
    (net (code "50") (name "PC6_D4") (class "Default")
      (node (ref "J9") (pin "5") (pinfunction "5_5") (pintype "passive"))
      (node (ref "U5") (pin "18") (pinfunction "PC6_18") (pintype "bidirectional"))
    )
    (net (code "51") (name "PC7_D31") (class "Default")
      (node (ref "U5") (pin "19") (pinfunction "PC7_19") (pintype "bidirectional"))
    )
    (net (code "52") (name "PD0_A0") (class "Default")
      (node (ref "J6") (pin "5") (pinfunction "5_5") (pintype "passive"))
      (node (ref "U5") (pin "20") (pinfunction "PD0_20") (pintype "bidirectional"))
    )
    (net (code "53") (name "PD1_A1") (class "Default")
      (node (ref "J6") (pin "6") (pinfunction "6_6") (pintype "passive"))
      (node (ref "U5") (pin "21") (pinfunction "PD1_21") (pintype "bidirectional"))
    )
    (net (code "54") (name "PD2_A2") (class "Default")
      (node (ref "J6") (pin "7") (pinfunction "7_7") (pintype "passive"))
      (node (ref "U5") (pin "22") (pinfunction "PD2_22") (pintype "bidirectional"))
    )
    (net (code "55") (name "PD3_A3") (class "Default")
      (node (ref "J6") (pin "8") (pinfunction "8_8") (pintype "passive"))
      (node (ref "U5") (pin "23") (pinfunction "PD3_23") (pintype "bidirectional"))
    )
    (net (code "56") (name "PD4_A4") (class "Default")
      (node (ref "J6") (pin "9") (pinfunction "9_9") (pintype "passive"))
      (node (ref "U5") (pin "24") (pinfunction "PD4_24") (pintype "bidirectional"))
    )
    (net (code "57") (name "PD5_A5") (class "Default")
      (node (ref "J6") (pin "10") (pinfunction "10_10") (pintype "passive"))
      (node (ref "U5") (pin "25") (pinfunction "PD5_25") (pintype "bidirectional"))
    )
    (net (code "58") (name "PD6_A6") (class "Default")
      (node (ref "D2") (pin "A") (pinfunction "A_A") (pintype "passive"))
      (node (ref "U5") (pin "26") (pinfunction "PD6_26") (pintype "bidirectional"))
    )
    (net (code "59") (name "PD7_A7_AREF") (class "Default")
      (node (ref "C11") (pin "1") (pinfunction "1_1") (pintype "passive"))
      (node (ref "C12") (pin "1") (pinfunction "1_1") (pintype "passive"))
      (node (ref "J9") (pin "16") (pinfunction "16_16") (pintype "passive"))
      (node (ref "U5") (pin "27") (pinfunction "PD7_27") (pintype "bidirectional"))
    )
    (net (code "60") (name "PE0_D11") (class "Default")
      (node (ref "J9") (pin "12") (pinfunction "12_12") (pintype "passive"))
      (node (ref "U5") (pin "30") (pinfunction "PE0_30") (pintype "bidirectional"))
    )
    (net (code "61") (name "PE1_D12") (class "Default")
      (node (ref "J9") (pin "13") (pinfunction "13_13") (pintype "passive"))
      (node (ref "U5") (pin "31") (pinfunction "PE1_31") (pintype "bidirectional"))
    )
    (net (code "62") (name "PE2_D13") (class "Default")
      (node (ref "J9") (pin "14") (pinfunction "14_14") (pintype "passive"))
      (node (ref "U5") (pin "32") (pinfunction "PE2_32") (pintype "bidirectional"))
    )
    (net (code "63") (name "PE3_D8") (class "Default")
      (node (ref "J9") (pin "9") (pinfunction "9_9") (pintype "passive"))
      (node (ref "U5") (pin "33") (pinfunction "PE3_33") (pintype "bidirectional"))
    )
    (net (code "64") (name "PF0_D37") (class "Default")
      (node (ref "U5") (pin "34") (pinfunction "PF0_34") (pintype "bidirectional"))
    )
    (net (code "65") (name "PF1_D38") (class "Default")
      (node (ref "U5") (pin "35") (pinfunction "PF1_35") (pintype "bidirectional"))
    )
    (net (code "66") (name "PF2_D35_A12") (class "Default")
      (node (ref "U5") (pin "36") (pinfunction "PF2_36") (pintype "bidirectional"))
      (node (ref "U6") (pin "5") (pinfunction "2A_5") (pintype "bidirectional"))
    )
    (net (code "67") (name "PF3_D36_A13") (class "Default")
      (node (ref "Q1") (pin "3") (pinfunction "D_3") (pintype "passive"))
      (node (ref "R4") (pin "6") (pinfunction "2_6") (pintype "passive"))
      (node (ref "U5") (pin "37") (pinfunction "PF3_37") (pintype "bidirectional"))
    )
    (net (code "68") (name "PF4_D6~{}") (class "Default")
      (node (ref "J9") (pin "7") (pinfunction "7_7") (pintype "passive"))
      (node (ref "U5") (pin "38") (pinfunction "PF4_38") (pintype "bidirectional"))
    )
    (net (code "69") (name "PF5_D3~{}") (class "Default")
      (node (ref "J9") (pin "4") (pinfunction "4_4") (pintype "passive"))
      (node (ref "U5") (pin "39") (pinfunction "PF5_39") (pintype "bidirectional"))
    )
    (net (code "70") (name "PF6_RST") (class "Default")
      (node (ref "J6") (pin "3") (pinfunction "3_3") (pintype "passive"))
      (node (ref "R13") (pin "1") (pinfunction "1_1") (pintype "passive"))
      (node (ref "SW1") (pin "2") (pinfunction "2_2") (pintype "bidirectional"))
      (node (ref "U5") (pin "40") (pinfunction "PF6_40") (pintype "bidirectional"))
    )
    (net (code "71") (name "RED") (class "Default")
      (node (ref "D1") (pin "5") (pinfunction "RED-A_5") (pintype "bidirectional"))
      (node (ref "R11") (pin "2") (pinfunction "2_2") (pintype "passive"))
    )
    (net (code "72") (name "RESETN") (class "Default")
      (node (ref "J9") (pin "19") (pinfunction "19_19") (pintype "passive"))
      (node (ref "R3") (pin "2") (pinfunction "1_2") (pintype "passive"))
      (node (ref "U4") (pin "11") (pinfunction "PA28/RESETN_11") (pintype "input"))
    )
    (net (code "73") (name "RX_D11") (class "Default")
      (node (ref "Q3") (pin "4") (pinfunction "S_4") (pintype "passive"))
      (node (ref "R3") (pin "3") (pinfunction "1_3") (pintype "passive"))
      (node (ref "U4") (pin "10") (pinfunction "PA23_10") (pintype "bidirectional"))
    )
    (net (code "74") (name "SWCLK") (class "Default")
      (node (ref "J6") (pin "2") (pinfunction "2_2") (pintype "passive"))
      (node (ref "R3") (pin "1") (pinfunction "1_1") (pintype "passive"))
      (node (ref "U4") (pin "12") (pinfunction "PA30/SWCLK_12") (pintype "bidirectional"))
    )
    (net (code "75") (name "SWDIO") (class "Default")
      (node (ref "J6") (pin "1") (pinfunction "1_1") (pintype "passive"))
      (node (ref "U4") (pin "13") (pinfunction "PA31/SWDIO_13") (pintype "bidirectional"))
    )
    (net (code "76") (name "TX_D11") (class "Default")
      (node (ref "Q3") (pin "1") (pinfunction "S_1") (pintype "passive"))
      (node (ref "R5") (pin "2") (pinfunction "1_2") (pintype "passive"))
      (node (ref "U4") (pin "9") (pinfunction "PA22_9") (pintype "bidirectional"))
    )
    (net (code "77") (name "UPDI_5V") (class "Default")
      (node (ref "Q2") (pin "6") (pinfunction "D_6") (pintype "passive"))
      (node (ref "R5") (pin "3") (pinfunction "1_3") (pintype "passive"))
      (node (ref "U5") (pin "41") (pinfunction "UPDI_41") (pintype "bidirectional"))
    )
    (net (code "78") (name "V_USB") (class "Default")
      (node (ref "F1") (pin "1") (pinfunction "1_1") (pintype "bidirectional"))
      (node (ref "J5") (pin "A4B9") (pinfunction "VBUS_A4B9") (pintype "power_in"))
      (node (ref "J5") (pin "B4A9") (pinfunction "VBUS_B4A9") (pintype "power_in"))
      (node (ref "TVS1") (pin "5") (pinfunction "VCC_5") (pintype "power_in"))
    )
    (net (code "79") (name "unconnected-(B1-*D3-PadD3)") (class "Default")
      (node (ref "B1") (pin "D3") (pinfunction "*D3_D3") (pintype "bidirectional"))
    )
    (net (code "80") (name "unconnected-(B1-*D5-PadD5)") (class "Default")
      (node (ref "B1") (pin "D5") (pinfunction "*D5_D5") (pintype "bidirectional"))
    )
    (net (code "81") (name "unconnected-(B1-*D6-PadD6)") (class "Default")
      (node (ref "B1") (pin "D6") (pinfunction "*D6_D6") (pintype "bidirectional"))
    )
    (net (code "82") (name "unconnected-(B1-*D9-PadD9)") (class "Default")
      (node (ref "B1") (pin "D9") (pinfunction "*D9_D9") (pintype "bidirectional"))
    )
    (net (code "83") (name "unconnected-(B1-*D10-PadD10)") (class "Default")
      (node (ref "B1") (pin "D10") (pinfunction "*D10_D10") (pintype "bidirectional"))
    )
    (net (code "84") (name "unconnected-(B1-*D11-PadD11)") (class "Default")
      (node (ref "B1") (pin "D11") (pinfunction "*D11_D11") (pintype "bidirectional"))
    )
    (net (code "85") (name "unconnected-(B1-GND-PadGND@1)") (class "Default")
      (node (ref "B1") (pin "GND@1") (pinfunction "GND_GND@1") (pintype "bidirectional"))
    )
    (net (code "86") (name "unconnected-(B1-GND-PadGND@2)") (class "Default")
      (node (ref "B1") (pin "GND@2") (pinfunction "GND_GND@2") (pintype "bidirectional"))
    )
    (net (code "87") (name "unconnected-(B1-GND-PadGND@3)") (class "Default")
      (node (ref "B1") (pin "GND@3") (pinfunction "GND_GND@3") (pintype "bidirectional"))
    )
    (net (code "88") (name "unconnected-(B1-GND-PadGND@4)") (class "Default")
      (node (ref "B1") (pin "GND@4") (pinfunction "GND_GND@4") (pintype "bidirectional"))
    )
    (net (code "89") (name "unconnected-(B1-Pad3.3V)") (class "Default")
      (node (ref "B1") (pin "3.3V") (pinfunction "3.3V_3.3V") (pintype "bidirectional"))
    )
    (net (code "90") (name "unconnected-(B1-Pad5V)") (class "Default")
      (node (ref "B1") (pin "5V") (pinfunction "5V_5V") (pintype "bidirectional"))
    )
    (net (code "91") (name "unconnected-(B1-PadA0)") (class "Default")
      (node (ref "B1") (pin "A0") (pinfunction "A0_A0") (pintype "bidirectional"))
    )
    (net (code "92") (name "unconnected-(B1-PadA1)") (class "Default")
      (node (ref "B1") (pin "A1") (pinfunction "A1_A1") (pintype "bidirectional"))
    )
    (net (code "93") (name "unconnected-(B1-PadA2)") (class "Default")
      (node (ref "B1") (pin "A2") (pinfunction "A2_A2") (pintype "bidirectional"))
    )
    (net (code "94") (name "unconnected-(B1-PadA3)") (class "Default")
      (node (ref "B1") (pin "A3") (pinfunction "A3_A3") (pintype "bidirectional"))
    )
    (net (code "95") (name "unconnected-(B1-PadA4)") (class "Default")
      (node (ref "B1") (pin "A4") (pinfunction "A4_A4") (pintype "bidirectional"))
    )
    (net (code "96") (name "unconnected-(B1-PadA5)") (class "Default")
      (node (ref "B1") (pin "A5") (pinfunction "A5_A5") (pintype "bidirectional"))
    )
    (net (code "97") (name "unconnected-(B1-PadAREF)") (class "Default")
      (node (ref "B1") (pin "AREF") (pinfunction "AREF_AREF") (pintype "bidirectional"))
    )
    (net (code "98") (name "unconnected-(B1-PadD0)") (class "Default")
      (node (ref "B1") (pin "D0") (pinfunction "D0_D0") (pintype "bidirectional"))
    )
    (net (code "99") (name "unconnected-(B1-PadD1)") (class "Default")
      (node (ref "B1") (pin "D1") (pinfunction "D1_D1") (pintype "bidirectional"))
    )
    (net (code "100") (name "unconnected-(B1-PadD2)") (class "Default")
      (node (ref "B1") (pin "D2") (pinfunction "D2_D2") (pintype "bidirectional"))
    )
    (net (code "101") (name "unconnected-(B1-PadD4)") (class "Default")
      (node (ref "B1") (pin "D4") (pinfunction "D4_D4") (pintype "bidirectional"))
    )
    (net (code "102") (name "unconnected-(B1-PadD7)") (class "Default")
      (node (ref "B1") (pin "D7") (pinfunction "D7_D7") (pintype "bidirectional"))
    )
    (net (code "103") (name "unconnected-(B1-PadD8)") (class "Default")
      (node (ref "B1") (pin "D8") (pinfunction "D8_D8") (pintype "bidirectional"))
    )
    (net (code "104") (name "unconnected-(B1-PadD12)") (class "Default")
      (node (ref "B1") (pin "D12") (pinfunction "D12_D12") (pintype "bidirectional"))
    )
    (net (code "105") (name "unconnected-(B1-PadD13)") (class "Default")
      (node (ref "B1") (pin "D13") (pinfunction "D13_D13") (pintype "bidirectional"))
    )
    (net (code "106") (name "unconnected-(B1-PadIOREF)") (class "Default")
      (node (ref "B1") (pin "IOREF") (pinfunction "IOREF_IOREF") (pintype "bidirectional"))
    )
    (net (code "107") (name "unconnected-(B1-PadMISO)") (class "Default")
      (node (ref "B1") (pin "MISO") (pinfunction "MISO_MISO") (pintype "bidirectional"))
    )
    (net (code "108") (name "unconnected-(B1-PadMOSI)") (class "Default")
      (node (ref "B1") (pin "MOSI") (pinfunction "MOSI_MOSI") (pintype "bidirectional"))
    )
    (net (code "109") (name "unconnected-(B1-PadSCK)") (class "Default")
      (node (ref "B1") (pin "SCK") (pinfunction "SCK_SCK") (pintype "bidirectional"))
    )
    (net (code "110") (name "unconnected-(B1-PadSCL)") (class "Default")
      (node (ref "B1") (pin "SCL") (pinfunction "SCL_SCL") (pintype "bidirectional"))
    )
    (net (code "111") (name "unconnected-(B1-PadSDA)") (class "Default")
      (node (ref "B1") (pin "SDA") (pinfunction "SDA_SDA") (pintype "bidirectional"))
    )
    (net (code "112") (name "unconnected-(B1-PadVCC)") (class "Default")
      (node (ref "B1") (pin "VCC") (pinfunction "VCC_VCC") (pintype "bidirectional"))
    )
    (net (code "113") (name "unconnected-(B1-PadVIN)") (class "Default")
      (node (ref "B1") (pin "VIN") (pinfunction "VIN_VIN") (pintype "bidirectional"))
    )
    (net (code "114") (name "unconnected-(B1-~{RESET}-PadRESET@1)") (class "Default")
      (node (ref "B1") (pin "RESET@1") (pinfunction "~{RESET}_RESET@1") (pintype "bidirectional"))
    )
    (net (code "115") (name "unconnected-(B1-~{RESET}-PadRESET@2)") (class "Default")
      (node (ref "B1") (pin "RESET@2") (pinfunction "~{RESET}_RESET@2") (pintype "bidirectional"))
    )
    (net (code "116") (name "unconnected-(J4-Pad1)") (class "Default")
      (node (ref "J4") (pin "1") (pinfunction "1_1") (pintype "passive"))
    )
    (net (code "117") (name "unconnected-(J4-Pad2)") (class "Default")
      (node (ref "J4") (pin "2") (pinfunction "2_2") (pintype "passive"))
    )
    (net (code "118") (name "unconnected-(J5-SBU1-PadA8)") (class "Default")
      (node (ref "J5") (pin "A8") (pinfunction "SBU1_A8") (pintype "bidirectional"))
    )
    (net (code "119") (name "unconnected-(J5-SBU2-PadB8)") (class "Default")
      (node (ref "J5") (pin "B8") (pinfunction "SBU2_B8") (pintype "bidirectional"))
    )
    (net (code "120") (name "unconnected-(TVS1-IO2-Pad3)") (class "Default")
      (node (ref "TVS1") (pin "3") (pinfunction "IO2_3") (pintype "passive"))
    )
    (net (code "121") (name "unconnected-(TVS1-IO4-Pad6)") (class "Default")
      (node (ref "TVS1") (pin "6") (pinfunction "IO4_6") (pintype "passive"))
    )
    (net (code "122") (name "unconnected-(U1-CLK-Pad20)") (class "Default")
      (node (ref "U1") (pin "20") (pinfunction "CLK_20") (pintype "bidirectional"))
    )
    (net (code "123") (name "unconnected-(U1-CMD-Pad19)") (class "Default")
      (node (ref "U1") (pin "19") (pinfunction "CMD_19") (pintype "bidirectional"))
    )
    (net (code "124") (name "unconnected-(U1-IO2-Pad24)") (class "Default")
      (node (ref "U1") (pin "24") (pinfunction "IO2_24") (pintype "bidirectional"))
    )
    (net (code "125") (name "unconnected-(U1-IO4-Pad26)") (class "Default")
      (node (ref "U1") (pin "26") (pinfunction "IO4_26") (pintype "bidirectional"))
    )
    (net (code "126") (name "unconnected-(U1-IO12-Pad14)") (class "Default")
      (node (ref "U1") (pin "14") (pinfunction "IO12_14") (pintype "bidirectional"))
    )
    (net (code "127") (name "unconnected-(U1-IO13-Pad16)") (class "Default")
      (node (ref "U1") (pin "16") (pinfunction "IO13_16") (pintype "bidirectional"))
    )
    (net (code "128") (name "unconnected-(U1-IO15-Pad23)") (class "Default")
      (node (ref "U1") (pin "23") (pinfunction "IO15_23") (pintype "bidirectional"))
    )
    (net (code "129") (name "unconnected-(U1-IO16-Pad27)") (class "Default")
      (node (ref "U1") (pin "27") (pinfunction "IO16_27") (pintype "bidirectional"))
    )
    (net (code "130") (name "unconnected-(U1-IO17-Pad28)") (class "Default")
      (node (ref "U1") (pin "28") (pinfunction "IO17_28") (pintype "bidirectional"))
    )
    (net (code "131") (name "unconnected-(U1-IO19-Pad31)") (class "Default")
      (node (ref "U1") (pin "31") (pinfunction "IO19_31") (pintype "bidirectional"))
    )
    (net (code "132") (name "unconnected-(U1-IO32-Pad8)") (class "Default")
      (node (ref "U1") (pin "8") (pinfunction "IO32_8") (pintype "bidirectional"))
    )
    (net (code "133") (name "unconnected-(U1-IO34-Pad6)") (class "Default")
      (node (ref "U1") (pin "6") (pinfunction "IO34_6") (pintype "bidirectional"))
    )
    (net (code "134") (name "unconnected-(U1-IO35-Pad7)") (class "Default")
      (node (ref "U1") (pin "7") (pinfunction "IO35_7") (pintype "bidirectional"))
    )
    (net (code "135") (name "unconnected-(U1-SD0-Pad21)") (class "Default")
      (node (ref "U1") (pin "21") (pinfunction "SD0_21") (pintype "bidirectional"))
    )
    (net (code "136") (name "unconnected-(U1-SD1-Pad22)") (class "Default")
      (node (ref "U1") (pin "22") (pinfunction "SD1_22") (pintype "bidirectional"))
    )
    (net (code "137") (name "unconnected-(U1-SD2-Pad17)") (class "Default")
      (node (ref "U1") (pin "17") (pinfunction "SD2_17") (pintype "bidirectional"))
    )
    (net (code "138") (name "unconnected-(U1-SD3-Pad18)") (class "Default")
      (node (ref "U1") (pin "18") (pinfunction "SD3_18") (pintype "bidirectional"))
    )
    (net (code "139") (name "unconnected-(U1-SVN-Pad5)") (class "Default")
      (node (ref "U1") (pin "5") (pinfunction "SVN_5") (pintype "bidirectional"))
    )
    (net (code "140") (name "unconnected-(U1-SVP-Pad4)") (class "Default")
      (node (ref "U1") (pin "4") (pinfunction "SVP_4") (pintype "bidirectional"))
    )
    (net (code "141") (name "unconnected-(U4-PA02-Pad18)") (class "Default")
      (node (ref "U4") (pin "18") (pinfunction "PA02_18") (pintype "bidirectional"))
    )
    (net (code "142") (name "unconnected-(U4-PA03-Pad19)") (class "Default")
      (node (ref "U4") (pin "19") (pinfunction "PA03_19") (pintype "bidirectional"))
    )
    (net (code "143") (name "unconnected-(U4-PA04-Pad20)") (class "Default")
      (node (ref "U4") (pin "20") (pinfunction "PA04_20") (pintype "bidirectional"))
    )
    (net (code "144") (name "unconnected-(U4-PA05-Pad1)") (class "Default")
      (node (ref "U4") (pin "1") (pinfunction "PA05_1") (pintype "bidirectional"))
    )
    (net (code "145") (name "unconnected-(U4-PA06-Pad2)") (class "Default")
      (node (ref "U4") (pin "2") (pinfunction "PA06_2") (pintype "bidirectional"))
    )
    (net (code "146") (name "unconnected-(U4-PA07-Pad3)") (class "Default")
      (node (ref "U4") (pin "3") (pinfunction "PA07_3") (pintype "bidirectional"))
    )
    (net (code "147") (name "unconnected-(U4-PA08{slash}XIN32-Pad4)") (class "Default")
      (node (ref "U4") (pin "4") (pinfunction "PA08/XIN32_4") (pintype "input"))
    )
    (net (code "148") (name "unconnected-(U4-PA09{slash}XOUT32-Pad5)") (class "Default")
      (node (ref "U4") (pin "5") (pinfunction "PA09/XOUT32_5") (pintype "input"))
    )
    (net (code "149") (name "unconnected-(U4-PA16-Pad8)") (class "Default")
      (node (ref "U4") (pin "8") (pinfunction "PA16_8") (pintype "bidirectional"))
    )
    (net (code "150") (name "unconnected-(U6-4A-Pad9)") (class "Default")
      (node (ref "U6") (pin "9") (pinfunction "4A_9") (pintype "bidirectional"))
    )
    (net (code "151") (name "unconnected-(U6-4Y-Pad10)") (class "Default")
      (node (ref "U6") (pin "10") (pinfunction "4Y_10") (pintype "bidirectional"))
    )
  )
)
